# Programming.net
KiCad netlist of a schematic drawn in Altium Designer
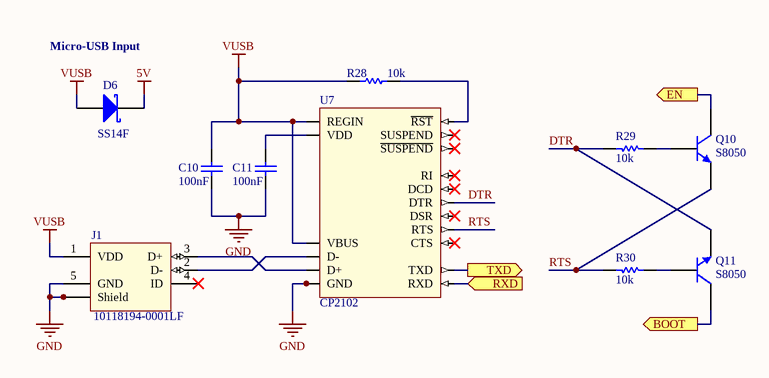
[diagram p0: Programming.SchDoc]

(export (version "E")
  (design (tool "Eeschema 10.0.6"))
  (components
    (comp (ref "C10")
      (value "100nF")
      (footprint "J1-0603")
      (description "Capacitor")
      (fields (field (name "Comment") "Cap") (field (name "PUBLISHER") "Altium Limited"))
      (libsource (lib "Miscellaneous Devices") (part "Cap"))
    )
    (comp (ref "C11")
      (value "100nF")
      (footprint "J1-0603")
      (description "Capacitor")
      (fields (field (name "Comment") "Cap") (field (name "PUBLISHER") "Altium Limited"))
      (libsource (lib "Miscellaneous Devices") (part "Cap"))
    )
    (comp (ref "D6")
      (value "SS14F")
      (footprint "SS14")
      (description "Schottky Diode")
      (fields (field (name "PUBLISHER") "Altium Limited"))
      (libsource (lib "Miscellaneous Devices") (part "D Schottky"))
    )
    (comp (ref "J1")
      (value "10118194-0001LF")
      (footprint "10103594-0001LF")
      (description "Conn Micro USB Type B RCP 5 POS 0.65mm Solder RA SMD 5 Terminal 1 Port T/R")
      (fields (field (name "MF") "FCI"))
      (libsource (lib "sumo") (part "10118194-0001LF_1"))
    )
    (comp (ref "Q10")
      (value "S8050")
      (footprint "SOT23-3M")
      (description "NPN General Purpose Amplifier")
      (fields (field (name "PUBLISHER") "Altium Limited"))
      (libsource (lib "sumo") (part "S8050"))
    )
    (comp (ref "Q11")
      (value "S8050")
      (footprint "SOT23-3M")
      (description "NPN General Purpose Amplifier")
      (fields (field (name "PUBLISHER") "Altium Limited"))
      (libsource (lib "sumo") (part "S8050"))
    )
    (comp (ref "R28")
      (value "10k")
      (footprint "J1-0603")
      (description "Resistor")
      (fields (field (name "Comment") "Res1") (field (name "PUBLISHER") "Altium Limited"))
      (libsource (lib "Miscellaneous Devices") (part "Res1"))
    )
    (comp (ref "R29")
      (value "10k")
      (footprint "J1-0603")
      (description "Resistor")
      (fields (field (name "Comment") "Res1") (field (name "PUBLISHER") "Altium Limited"))
      (libsource (lib "Miscellaneous Devices") (part "Res1"))
    )
    (comp (ref "R30")
      (value "10k")
      (footprint "J1-0603")
      (description "Resistor")
      (fields (field (name "Comment") "Res1") (field (name "PUBLISHER") "Altium Limited"))
      (libsource (lib "Miscellaneous Devices") (part "Res1"))
    )
    (comp (ref "U7") (value "CP2102") (footprint "QFN-28") (libsource (lib "sumo") (part "CP2102")))
  )
  (nets
    (net (code "1") (name "/BOOT") (class "Default")
      (node (ref "Q11") (pin "3") (pinfunction "C_3") (pintype "passive"))
    )
    (net (code "2") (name "/DTR") (class "Default")
      (node (ref "Q11") (pin "2") (pinfunction "E_2") (pintype "passive"))
      (node (ref "R29") (pin "1") (pinfunction "1_1") (pintype "passive"))
      (node (ref "U7") (pin "28") (pinfunction "DTR_28") (pintype "output"))
    )
    (net (code "3") (name "/EN") (class "Default")
      (node (ref "Q10") (pin "3") (pinfunction "C_3") (pintype "passive"))
    )
    (net (code "4") (name "/RTS") (class "Default")
      (node (ref "Q10") (pin "2") (pinfunction "E_2") (pintype "passive"))
      (node (ref "R30") (pin "1") (pinfunction "1_1") (pintype "passive"))
      (node (ref "U7") (pin "24") (pinfunction "RTS_24") (pintype "output"))
    )
    (net (code "5") (name "/RXD") (class "Default")
      (node (ref "U7") (pin "25") (pinfunction "RXD_25") (pintype "input"))
    )
    (net (code "6") (name "/TXD") (class "Default")
      (node (ref "U7") (pin "26") (pinfunction "TXD_26") (pintype "output"))
    )
    (net (code "7") (name "5V") (class "Default")
      (node (ref "D6") (pin "2") (pinfunction "K_2") (pintype "passive"))
    )
    (net (code "8") (name "GND") (class "Default")
      (node (ref "C10") (pin "1") (pinfunction "1_1") (pintype "passive"))
      (node (ref "C11") (pin "1") (pinfunction "1_1") (pintype "passive"))
      (node (ref "J1") (pin "5") (pinfunction "GND_5") (pintype "power_in"))
      (node (ref "J1") (pin "6") (pinfunction "Shield_6") (pintype "power_in"))
      (node (ref "J1") (pin "7") (pinfunction "Shield_7") (pintype "power_in"))
      (node (ref "J1") (pin "8") (pinfunction "Shield_8") (pintype "power_in"))
      (node (ref "J1") (pin "9") (pinfunction "Shield_9") (pintype "power_in"))
      (node (ref "U7") (pin "29") (pinfunction "29_29") (pintype "power_in"))
      (node (ref "U7") (pin "3") (pinfunction "GND_3") (pintype "power_in"))
    )
    (net (code "9") (name "Net-(J1-D+)") (class "Default")
      (node (ref "J1") (pin "3") (pinfunction "D+_3") (pintype "bidirectional"))
      (node (ref "U7") (pin "4") (pinfunction "D+_4") (pintype "bidirectional"))
    )
    (net (code "10") (name "Net-(J1-D-)") (class "Default")
      (node (ref "J1") (pin "2") (pinfunction "D-_2") (pintype "bidirectional"))
      (node (ref "U7") (pin "5") (pinfunction "D-_5") (pintype "bidirectional"))
    )
    (net (code "11") (name "Net-(Q10-B)") (class "Default")
      (node (ref "Q10") (pin "1") (pinfunction "B_1") (pintype "passive"))
      (node (ref "R29") (pin "2") (pinfunction "2_2") (pintype "passive"))
    )
    (net (code "12") (name "Net-(Q11-B)") (class "Default")
      (node (ref "Q11") (pin "1") (pinfunction "B_1") (pintype "passive"))
      (node (ref "R30") (pin "2") (pinfunction "2_2") (pintype "passive"))
    )
    (net (code "13") (name "Net-(U7-VDD)") (class "Default")
      (node (ref "C11") (pin "2") (pinfunction "2_2") (pintype "passive"))
      (node (ref "U7") (pin "6") (pinfunction "VDD_6") (pintype "power_in"))
    )
    (net (code "14") (name "Net-(U7-~{RST})") (class "Default")
      (node (ref "R28") (pin "1") (pinfunction "1_1") (pintype "passive"))
      (node (ref "U7") (pin "9") (pinfunction "~{RST}_9") (pintype "input"))
    )
    (net (code "15") (name "VUSB") (class "Default")
      (node (ref "C10") (pin "2") (pinfunction "2_2") (pintype "passive"))
      (node (ref "D6") (pin "1") (pinfunction "A_1") (pintype "passive"))
      (node (ref "J1") (pin "1") (pinfunction "VDD_1") (pintype "power_in"))
      (node (ref "R28") (pin "2") (pinfunction "2_2") (pintype "passive"))
      (node (ref "U7") (pin "7") (pinfunction "REGIN_7") (pintype "power_in"))
      (node (ref "U7") (pin "8") (pinfunction "VBUS_8") (pintype "power_in"))
    )
    (net (code "16") (name "unconnected-(J1-ID-Pad4)") (class "Default")
      (node (ref "J1") (pin "4") (pinfunction "ID_4") (pintype "passive+no_connect"))
    )
    (net (code "17") (name "unconnected-(U7-CTS-Pad23)") (class "Default")
      (node (ref "U7") (pin "23") (pinfunction "CTS_23") (pintype "input+no_connect"))
    )
    (net (code "18") (name "unconnected-(U7-DCD-Pad1)") (class "Default")
      (node (ref "U7") (pin "1") (pinfunction "DCD_1") (pintype "input+no_connect"))
    )
    (net (code "19") (name "unconnected-(U7-DSR-Pad27)") (class "Default")
      (node (ref "U7") (pin "27") (pinfunction "DSR_27") (pintype "input+no_connect"))
    )
    (net (code "20") (name "unconnected-(U7-RI-Pad2)") (class "Default")
      (node (ref "U7") (pin "2") (pinfunction "RI_2") (pintype "input+no_connect"))
    )
    (net (code "21") (name "unconnected-(U7-SUSPEND-Pad12)") (class "Default")
      (node (ref "U7") (pin "12") (pinfunction "SUSPEND_12") (pintype "output+no_connect"))
    )
    (net (code "22") (name "unconnected-(U7-~{SUSPEND}-Pad11)") (class "Default")
      (node (ref "U7") (pin "11") (pinfunction "~{SUSPEND}_11") (pintype "output+no_connect"))
    )
  )
)
